# graphic_stereo_2.net
KiCad netlist of a schematic drawn in EAGLE
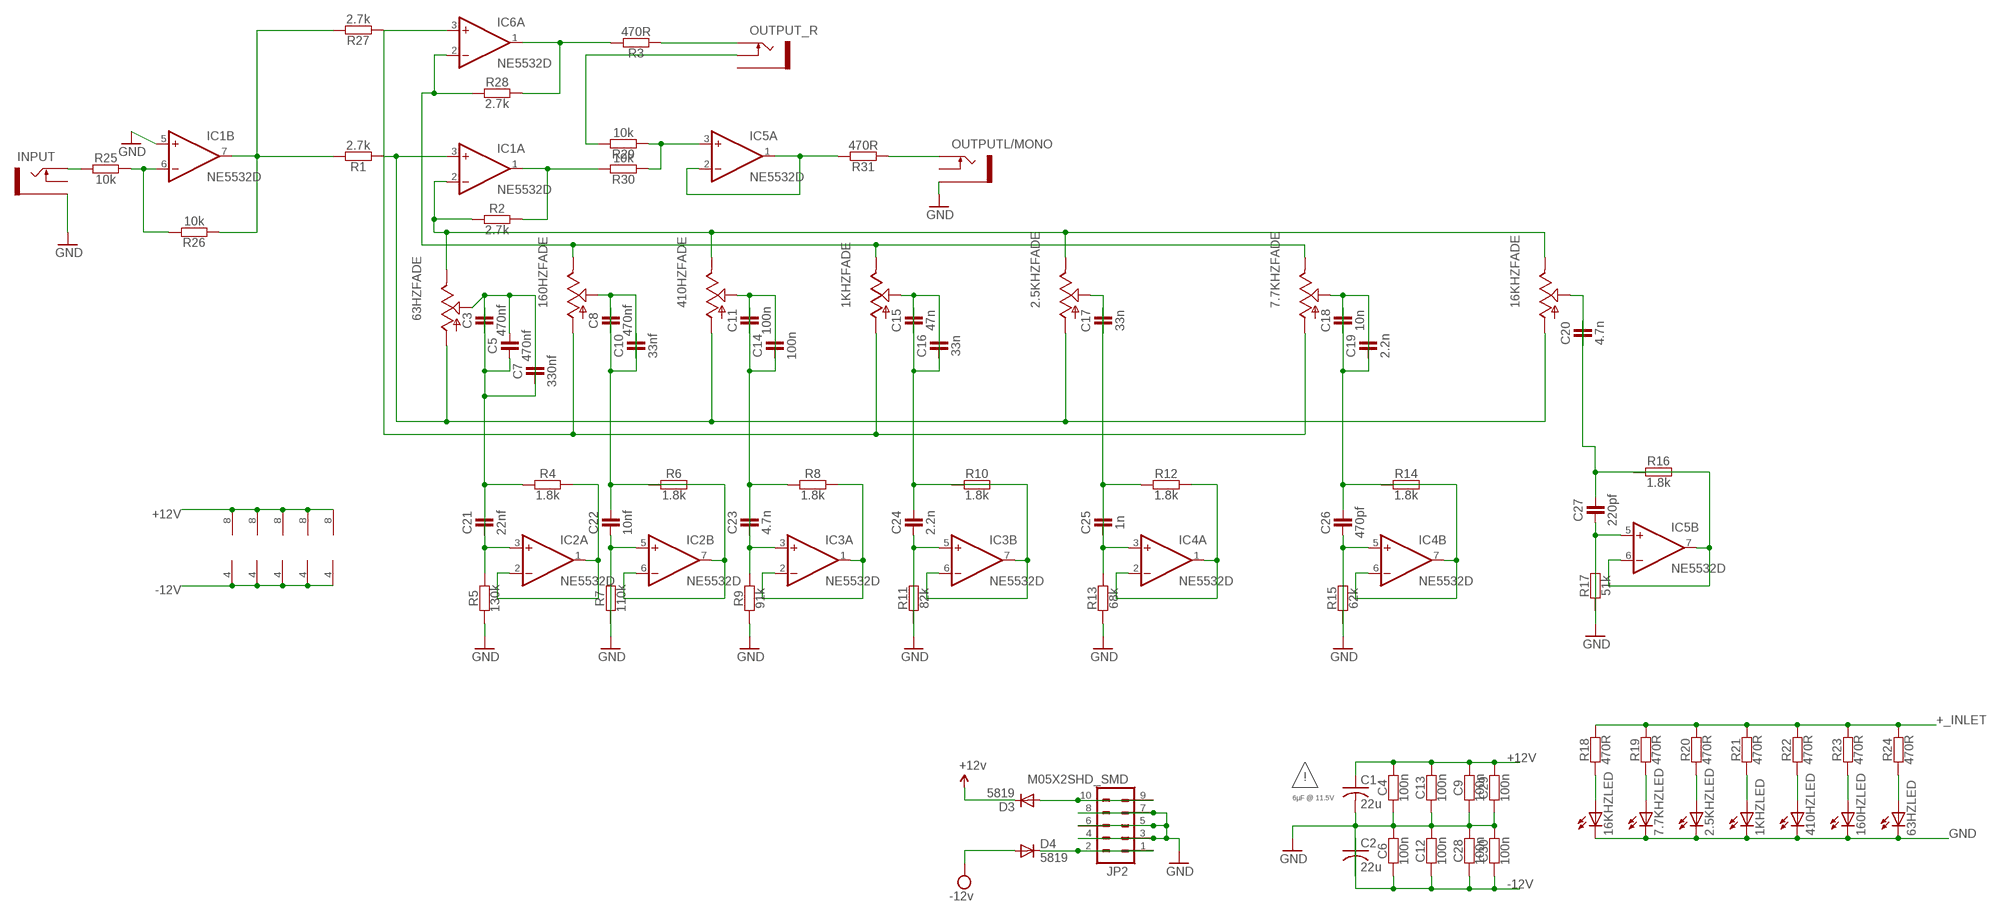
[diagram p0: schematic, sheet 1]

(export (version "E")
  (design (tool "Eeschema 10.0.6"))
  (components
    (comp (ref "1KHZ")
      (value "ALPHA_20MM_ILLUM_FADER")
      (footprint "eagle-import:ALPHA_ILL_FADER_20MM")
      (libsource (lib "eagle-import") (part "ALPHA_20MM_ILLUM_FADER"))
    )
    (comp (ref "2.5KHZ")
      (value "ALPHA_20MM_ILLUM_FADER")
      (footprint "eagle-import:ALPHA_ILL_FADER_20MM")
      (libsource (lib "eagle-import") (part "ALPHA_20MM_ILLUM_FADER"))
    )
    (comp (ref "7.7KHZ")
      (value "ALPHA_20MM_ILLUM_FADER")
      (footprint "eagle-import:ALPHA_ILL_FADER_20MM")
      (libsource (lib "eagle-import") (part "ALPHA_20MM_ILLUM_FADER"))
    )
    (comp (ref "16KHZ")
      (value "ALPHA_20MM_ILLUM_FADER")
      (footprint "eagle-import:ALPHA_ILL_FADER_20MM")
      (libsource (lib "eagle-import") (part "ALPHA_20MM_ILLUM_FADER"))
    )
    (comp (ref "63HZ")
      (value "ALPHA_20MM_ILLUM_FADER")
      (footprint "eagle-import:ALPHA_ILL_FADER_20MM")
      (libsource (lib "eagle-import") (part "ALPHA_20MM_ILLUM_FADER"))
    )
    (comp (ref "160HZ")
      (value "ALPHA_20MM_ILLUM_FADER")
      (footprint "eagle-import:ALPHA_ILL_FADER_20MM")
      (libsource (lib "eagle-import") (part "ALPHA_20MM_ILLUM_FADER"))
    )
    (comp (ref "410HZ")
      (value "ALPHA_20MM_ILLUM_FADER")
      (footprint "eagle-import:ALPHA_ILL_FADER_20MM")
      (libsource (lib "eagle-import") (part "ALPHA_20MM_ILLUM_FADER"))
    )
    (comp (ref "C1")
      (value "22u")
      (footprint "eagle-import:C1206")
      (libsource (lib "eagle-import") (part "C-USC1206"))
    )
    (comp (ref "C2")
      (value "22u")
      (footprint "eagle-import:C1206")
      (libsource (lib "eagle-import") (part "C-USC1206"))
    )
    (comp (ref "C3")
      (value "470nf")
      (footprint "eagle-import:C0805")
      (libsource (lib "eagle-import") (part "CAPACITOR-0805"))
    )
    (comp (ref "C4")
      (value "100n")
      (footprint "eagle-import:C0805")
      (libsource (lib "eagle-import") (part "RESISTOR-0805"))
    )
    (comp (ref "C5")
      (value "470nf")
      (footprint "eagle-import:C0805")
      (libsource (lib "eagle-import") (part "CAPACITOR-0805"))
    )
    (comp (ref "C6")
      (value "100n")
      (footprint "eagle-import:C0805")
      (libsource (lib "eagle-import") (part "RESISTOR-0805"))
    )
    (comp (ref "C7")
      (value "330nf")
      (footprint "eagle-import:C0805")
      (libsource (lib "eagle-import") (part "CAPACITOR-0805"))
    )
    (comp (ref "C8")
      (value "470nf")
      (footprint "eagle-import:C0805")
      (libsource (lib "eagle-import") (part "CAPACITOR-0805"))
    )
    (comp (ref "C9")
      (value "100n")
      (footprint "eagle-import:C0805")
      (libsource (lib "eagle-import") (part "RESISTOR-0805"))
    )
    (comp (ref "C10")
      (value "33nf")
      (footprint "eagle-import:C0805")
      (libsource (lib "eagle-import") (part "CAPACITOR-0805"))
    )
    (comp (ref "C11")
      (value "100n")
      (footprint "eagle-import:C0805")
      (libsource (lib "eagle-import") (part "CAPACITOR-0805"))
    )
    (comp (ref "C12")
      (value "100n")
      (footprint "eagle-import:C0805")
      (libsource (lib "eagle-import") (part "RESISTOR-0805"))
    )
    (comp (ref "C13")
      (value "100n")
      (footprint "eagle-import:C0805")
      (libsource (lib "eagle-import") (part "RESISTOR-0805"))
    )
    (comp (ref "C14")
      (value "100n")
      (footprint "eagle-import:C0805")
      (libsource (lib "eagle-import") (part "CAPACITOR-0805"))
    )
    (comp (ref "C15")
      (value "47n")
      (footprint "eagle-import:C0805")
      (libsource (lib "eagle-import") (part "CAPACITOR-0805"))
    )
    (comp (ref "C16")
      (value "33n")
      (footprint "eagle-import:C0805")
      (libsource (lib "eagle-import") (part "CAPACITOR-0805"))
    )
    (comp (ref "C17")
      (value "33n")
      (footprint "eagle-import:C0805")
      (libsource (lib "eagle-import") (part "CAPACITOR-0805"))
    )
    (comp (ref "C18")
      (value "10n")
      (footprint "eagle-import:C0805")
      (libsource (lib "eagle-import") (part "CAPACITOR-0805"))
    )
    (comp (ref "C19")
      (value "2.2n")
      (footprint "eagle-import:C0805")
      (libsource (lib "eagle-import") (part "CAPACITOR-0805"))
    )
    (comp (ref "C20")
      (value "4.7n")
      (footprint "eagle-import:C0805")
      (libsource (lib "eagle-import") (part "CAPACITOR-0805"))
    )
    (comp (ref "C21")
      (value "22nf")
      (footprint "eagle-import:C0805")
      (libsource (lib "eagle-import") (part "CAPACITOR-0805"))
    )
    (comp (ref "C22")
      (value "10nf")
      (footprint "eagle-import:C0805")
      (libsource (lib "eagle-import") (part "CAPACITOR-0805"))
    )
    (comp (ref "C23")
      (value "4.7n")
      (footprint "eagle-import:C0805")
      (libsource (lib "eagle-import") (part "CAPACITOR-0805"))
    )
    (comp (ref "C24")
      (value "2.2n")
      (footprint "eagle-import:C0805")
      (libsource (lib "eagle-import") (part "CAPACITOR-0805"))
    )
    (comp (ref "C25")
      (value "1n")
      (footprint "eagle-import:C0805")
      (libsource (lib "eagle-import") (part "CAPACITOR-0805"))
    )
    (comp (ref "C26")
      (value "470pf")
      (footprint "eagle-import:C0805")
      (libsource (lib "eagle-import") (part "CAPACITOR-0805"))
    )
    (comp (ref "C27")
      (value "220pf")
      (footprint "eagle-import:C0805")
      (libsource (lib "eagle-import") (part "CAPACITOR-0805"))
    )
    (comp (ref "C28")
      (value "100n")
      (footprint "eagle-import:C0805")
      (libsource (lib "eagle-import") (part "RESISTOR-0805"))
    )
    (comp (ref "C29")
      (value "100n")
      (footprint "eagle-import:C0805")
      (libsource (lib "eagle-import") (part "RESISTOR-0805"))
    )
    (comp (ref "C30")
      (value "100n")
      (footprint "eagle-import:C0805")
      (libsource (lib "eagle-import") (part "RESISTOR-0805"))
    )
    (comp (ref "D3")
      (value "5819")
      (footprint "eagle-import:SOD123")
      (libsource (lib "eagle-import") (part "DIODE-SOD123"))
    )
    (comp (ref "D4")
      (value "5819")
      (footprint "eagle-import:SOD123")
      (libsource (lib "eagle-import") (part "DIODE-SOD123"))
    )
    (comp (ref "IC1")
      (value "NE5532D")
      (footprint "eagle-import:SO08")
      (libsource (lib "eagle-import") (part "NE5532D"))
    )
    (comp (ref "IC2")
      (value "NE5532D")
      (footprint "eagle-import:SO08")
      (libsource (lib "eagle-import") (part "NE5532D"))
    )
    (comp (ref "IC3")
      (value "NE5532D")
      (footprint "eagle-import:SO08")
      (libsource (lib "eagle-import") (part "NE5532D"))
    )
    (comp (ref "IC4")
      (value "NE5532D")
      (footprint "eagle-import:SO08")
      (libsource (lib "eagle-import") (part "NE5532D"))
    )
    (comp (ref "IC5")
      (value "NE5532D")
      (footprint "eagle-import:SO08")
      (libsource (lib "eagle-import") (part "NE5532D"))
    )
    (comp (ref "IC6")
      (value "NE5532D")
      (footprint "eagle-import:SO08")
      (libsource (lib "eagle-import") (part "NE5532D"))
    )
    (comp (ref "INPUT")
      (value "THONKICONNNEW")
      (footprint "eagle-import:WQP-PJ301M-12_JACK")
      (libsource (lib "eagle-import") (part "THONKICONNNEW"))
    )
    (comp (ref "JP2")
      (value "M05X2SHD_SMD")
      (footprint "eagle-import:2X5-SHROUDED_SMD")
      (libsource (lib "eagle-import") (part "M05X2SHD_SMD"))
    )
    (comp (ref "OUTPUTL/MONO")
      (value "THONKICONNNEW")
      (footprint "eagle-import:WQP-PJ301M-12_JACK")
      (libsource (lib "eagle-import") (part "THONKICONNNEW"))
    )
    (comp (ref "OUTPUT_R")
      (value "THONKICONNNEW")
      (footprint "eagle-import:WQP-PJ301M-12_JACK")
      (libsource (lib "eagle-import") (part "THONKICONNNEW"))
    )
    (comp (ref "R1")
      (value "2.7k")
      (footprint "eagle-import:C0805")
      (libsource (lib "eagle-import") (part "RESISTOR-0805"))
    )
    (comp (ref "R2")
      (value "2.7k")
      (footprint "eagle-import:C0805")
      (libsource (lib "eagle-import") (part "RESISTOR-0805"))
    )
    (comp (ref "R3")
      (value "470R")
      (footprint "eagle-import:C0805")
      (libsource (lib "eagle-import") (part "RESISTOR-0805"))
    )
    (comp (ref "R4")
      (value "1.8k")
      (footprint "eagle-import:C0805")
      (libsource (lib "eagle-import") (part "RESISTOR-0805"))
    )
    (comp (ref "R5")
      (value "130k")
      (footprint "eagle-import:C0805")
      (libsource (lib "eagle-import") (part "RESISTOR-0805"))
    )
    (comp (ref "R6")
      (value "1.8k")
      (footprint "eagle-import:C0805")
      (libsource (lib "eagle-import") (part "RESISTOR-0805"))
    )
    (comp (ref "R7")
      (value "110k")
      (footprint "eagle-import:C0805")
      (libsource (lib "eagle-import") (part "RESISTOR-0805"))
    )
    (comp (ref "R8")
      (value "1.8k")
      (footprint "eagle-import:C0805")
      (libsource (lib "eagle-import") (part "RESISTOR-0805"))
    )
    (comp (ref "R9")
      (value "91k")
      (footprint "eagle-import:C0805")
      (libsource (lib "eagle-import") (part "RESISTOR-0805"))
    )
    (comp (ref "R10")
      (value "1.8k")
      (footprint "eagle-import:C0805")
      (libsource (lib "eagle-import") (part "RESISTOR-0805"))
    )
    (comp (ref "R11")
      (value "82k")
      (footprint "eagle-import:C0805")
      (libsource (lib "eagle-import") (part "RESISTOR-0805"))
    )
    (comp (ref "R12")
      (value "1.8k")
      (footprint "eagle-import:C0805")
      (libsource (lib "eagle-import") (part "RESISTOR-0805"))
    )
    (comp (ref "R13")
      (value "68k")
      (footprint "eagle-import:C0805")
      (libsource (lib "eagle-import") (part "RESISTOR-0805"))
    )
    (comp (ref "R14")
      (value "1.8k")
      (footprint "eagle-import:C0805")
      (libsource (lib "eagle-import") (part "RESISTOR-0805"))
    )
    (comp (ref "R15")
      (value "62k")
      (footprint "eagle-import:C0805")
      (libsource (lib "eagle-import") (part "RESISTOR-0805"))
    )
    (comp (ref "R16")
      (value "1.8k")
      (footprint "eagle-import:C0805")
      (libsource (lib "eagle-import") (part "RESISTOR-0805"))
    )
    (comp (ref "R17")
      (value "51k")
      (footprint "eagle-import:C0805")
      (libsource (lib "eagle-import") (part "RESISTOR-0805"))
    )
    (comp (ref "R18")
      (value "470R")
      (footprint "eagle-import:C0805")
      (libsource (lib "eagle-import") (part "RESISTOR-0805"))
    )
    (comp (ref "R19")
      (value "470R")
      (footprint "eagle-import:C0805")
      (libsource (lib "eagle-import") (part "RESISTOR-0805"))
    )
    (comp (ref "R20")
      (value "470R")
      (footprint "eagle-import:C0805")
      (libsource (lib "eagle-import") (part "RESISTOR-0805"))
    )
    (comp (ref "R21")
      (value "470R")
      (footprint "eagle-import:C0805")
      (libsource (lib "eagle-import") (part "RESISTOR-0805"))
    )
    (comp (ref "R22")
      (value "470R")
      (footprint "eagle-import:C0805")
      (libsource (lib "eagle-import") (part "RESISTOR-0805"))
    )
    (comp (ref "R23")
      (value "470R")
      (footprint "eagle-import:C0805")
      (libsource (lib "eagle-import") (part "RESISTOR-0805"))
    )
    (comp (ref "R24")
      (value "470R")
      (footprint "eagle-import:C0805")
      (libsource (lib "eagle-import") (part "RESISTOR-0805"))
    )
    (comp (ref "R25")
      (value "10k")
      (footprint "eagle-import:C0805")
      (libsource (lib "eagle-import") (part "RESISTOR-0805"))
    )
    (comp (ref "R26")
      (value "10k")
      (footprint "eagle-import:C0805")
      (libsource (lib "eagle-import") (part "RESISTOR-0805"))
    )
    (comp (ref "R27")
      (value "2.7k")
      (footprint "eagle-import:C0805")
      (libsource (lib "eagle-import") (part "RESISTOR-0805"))
    )
    (comp (ref "R28")
      (value "2.7k")
      (footprint "eagle-import:C0805")
      (libsource (lib "eagle-import") (part "RESISTOR-0805"))
    )
    (comp (ref "R29")
      (value "10k")
      (footprint "eagle-import:C0805")
      (libsource (lib "eagle-import") (part "RESISTOR-0805"))
    )
    (comp (ref "R30")
      (value "10k")
      (footprint "eagle-import:C0805")
      (libsource (lib "eagle-import") (part "RESISTOR-0805"))
    )
    (comp (ref "R31")
      (value "470R")
      (footprint "eagle-import:C0805")
      (libsource (lib "eagle-import") (part "RESISTOR-0805"))
    )
  )
  (nets
    (net (code "1") (name "+12v") (class "Default")
      (node (ref "C1") (pin "1") (pinfunction "1_1") (pintype "passive"))
      (node (ref "C13") (pin "2") (pinfunction "2_2") (pintype "passive"))
      (node (ref "C29") (pin "2") (pinfunction "2_2") (pintype "passive"))
      (node (ref "C4") (pin "2") (pinfunction "2_2") (pintype "passive"))
      (node (ref "C9") (pin "2") (pinfunction "2_2") (pintype "passive"))
      (node (ref "D3") (pin "C") (pinfunction "C_C") (pintype "passive"))
      (node (ref "IC1") (pin "8") (pinfunction "V+_8") (pintype "power_in"))
      (node (ref "IC2") (pin "8") (pinfunction "V+_8") (pintype "power_in"))
      (node (ref "IC3") (pin "8") (pinfunction "V+_8") (pintype "power_in"))
      (node (ref "IC4") (pin "8") (pinfunction "V+_8") (pintype "power_in"))
      (node (ref "IC5") (pin "8") (pinfunction "V+_8") (pintype "power_in"))
    )
    (net (code "2") (name "-12v") (class "Default")
      (node (ref "C12") (pin "1") (pinfunction "1_1") (pintype "passive"))
      (node (ref "C2") (pin "1") (pinfunction "1_1") (pintype "passive"))
      (node (ref "C28") (pin "1") (pinfunction "1_1") (pintype "passive"))
      (node (ref "C30") (pin "1") (pinfunction "1_1") (pintype "passive"))
      (node (ref "C6") (pin "1") (pinfunction "1_1") (pintype "passive"))
      (node (ref "D4") (pin "A") (pinfunction "A_A") (pintype "passive"))
      (node (ref "IC1") (pin "4") (pinfunction "V-_4") (pintype "power_in"))
      (node (ref "IC2") (pin "4") (pinfunction "V-_4") (pintype "power_in"))
      (node (ref "IC3") (pin "4") (pinfunction "V-_4") (pintype "power_in"))
      (node (ref "IC4") (pin "4") (pinfunction "V-_4") (pintype "power_in"))
      (node (ref "IC5") (pin "4") (pinfunction "V-_4") (pintype "power_in"))
    )
    (net (code "3") (name "/+_INLET") (class "Default")
      (node (ref "D3") (pin "A") (pinfunction "A_A") (pintype "passive"))
      (node (ref "JP2") (pin "10") (pinfunction "10_10") (pintype "passive"))
      (node (ref "JP2") (pin "9") (pinfunction "9_9") (pintype "passive"))
      (node (ref "R18") (pin "2") (pinfunction "2_2") (pintype "passive"))
      (node (ref "R19") (pin "2") (pinfunction "2_2") (pintype "passive"))
      (node (ref "R20") (pin "2") (pinfunction "2_2") (pintype "passive"))
      (node (ref "R21") (pin "2") (pinfunction "2_2") (pintype "passive"))
      (node (ref "R22") (pin "2") (pinfunction "2_2") (pintype "passive"))
      (node (ref "R23") (pin "2") (pinfunction "2_2") (pintype "passive"))
      (node (ref "R24") (pin "2") (pinfunction "2_2") (pintype "passive"))
    )
    (net (code "4") (name "GND") (class "Default")
      (node (ref "160HZ") (pin "E") (pinfunction "C_E") (pintype "passive"))
      (node (ref "16KHZ") (pin "E") (pinfunction "C_E") (pintype "passive"))
      (node (ref "1KHZ") (pin "E") (pinfunction "C_E") (pintype "passive"))
      (node (ref "2.5KHZ") (pin "E") (pinfunction "C_E") (pintype "passive"))
      (node (ref "410HZ") (pin "E") (pinfunction "C_E") (pintype "passive"))
      (node (ref "63HZ") (pin "E") (pinfunction "C_E") (pintype "passive"))
      (node (ref "7.7KHZ") (pin "E") (pinfunction "C_E") (pintype "passive"))
      (node (ref "C1") (pin "2") (pinfunction "2_2") (pintype "passive"))
      (node (ref "C12") (pin "2") (pinfunction "2_2") (pintype "passive"))
      (node (ref "C13") (pin "1") (pinfunction "1_1") (pintype "passive"))
      (node (ref "C2") (pin "2") (pinfunction "2_2") (pintype "passive"))
      (node (ref "C28") (pin "2") (pinfunction "2_2") (pintype "passive"))
      (node (ref "C29") (pin "1") (pinfunction "1_1") (pintype "passive"))
      (node (ref "C30") (pin "2") (pinfunction "2_2") (pintype "passive"))
      (node (ref "C4") (pin "1") (pinfunction "1_1") (pintype "passive"))
      (node (ref "C6") (pin "2") (pinfunction "2_2") (pintype "passive"))
      (node (ref "C9") (pin "1") (pinfunction "1_1") (pintype "passive"))
      (node (ref "IC1") (pin "5") (pinfunction "+IN_5") (pintype "input"))
      (node (ref "INPUT") (pin "P$3_SLEEVE") (pinfunction "SLEEVE_P$3_SLEEVE") (pintype "passive"))
      (node (ref "JP2") (pin "3") (pinfunction "3_3") (pintype "passive"))
      (node (ref "JP2") (pin "4") (pinfunction "4_4") (pintype "passive"))
      (node (ref "JP2") (pin "5") (pinfunction "5_5") (pintype "passive"))
      (node (ref "JP2") (pin "6") (pinfunction "6_6") (pintype "passive"))
      (node (ref "JP2") (pin "7") (pinfunction "7_7") (pintype "passive"))
      (node (ref "JP2") (pin "8") (pinfunction "8_8") (pintype "passive"))
      (node (ref "OUTPUTL/MONO") (pin "P$3_SLEEVE") (pinfunction "SLEEVE_P$3_SLEEVE") (pintype "passive"))
      (node (ref "R11") (pin "2") (pinfunction "2_2") (pintype "passive"))
      (node (ref "R13") (pin "1") (pinfunction "1_1") (pintype "passive"))
      (node (ref "R15") (pin "2") (pinfunction "2_2") (pintype "passive"))
      (node (ref "R17") (pin "2") (pinfunction "2_2") (pintype "passive"))
      (node (ref "R5") (pin "1") (pinfunction "1_1") (pintype "passive"))
      (node (ref "R7") (pin "2") (pinfunction "2_2") (pintype "passive"))
      (node (ref "R9") (pin "1") (pinfunction "1_1") (pintype "passive"))
    )
    (net (code "5") (name "Net-(1KHZA-S)") (class "Default")
      (node (ref "1KHZ") (pin "2") (pinfunction "S_2") (pintype "passive"))
      (node (ref "C15") (pin "1") (pinfunction "1_1") (pintype "passive"))
      (node (ref "C16") (pin "1") (pinfunction "1_1") (pintype "passive"))
    )
    (net (code "6") (name "Net-(1KHZB-A)") (class "Default")
      (node (ref "1KHZ") (pin "B") (pinfunction "A_B") (pintype "passive"))
      (node (ref "R21") (pin "1") (pinfunction "1_1") (pintype "passive"))
    )
    (net (code "7") (name "Net-(2.5KHZA-S)") (class "Default")
      (node (ref "2.5KHZ") (pin "2") (pinfunction "S_2") (pintype "passive"))
      (node (ref "C17") (pin "1") (pinfunction "1_1") (pintype "passive"))
    )
    (net (code "8") (name "Net-(2.5KHZB-A)") (class "Default")
      (node (ref "2.5KHZ") (pin "B") (pinfunction "A_B") (pintype "passive"))
      (node (ref "R20") (pin "1") (pinfunction "1_1") (pintype "passive"))
    )
    (net (code "9") (name "Net-(7.7KHZA-S)") (class "Default")
      (node (ref "7.7KHZ") (pin "2") (pinfunction "S_2") (pintype "passive"))
      (node (ref "C18") (pin "1") (pinfunction "1_1") (pintype "passive"))
      (node (ref "C19") (pin "1") (pinfunction "1_1") (pintype "passive"))
    )
    (net (code "10") (name "Net-(7.7KHZB-A)") (class "Default")
      (node (ref "7.7KHZ") (pin "B") (pinfunction "A_B") (pintype "passive"))
      (node (ref "R19") (pin "1") (pinfunction "1_1") (pintype "passive"))
    )
    (net (code "11") (name "Net-(16KHZA-A)") (class "Default")
      (node (ref "16KHZ") (pin "3") (pinfunction "A_3") (pintype "passive"))
      (node (ref "2.5KHZ") (pin "3") (pinfunction "A_3") (pintype "passive"))
      (node (ref "410HZ") (pin "3") (pinfunction "A_3") (pintype "passive"))
      (node (ref "63HZ") (pin "3") (pinfunction "A_3") (pintype "passive"))
      (node (ref "IC1") (pin "3") (pinfunction "+IN_3") (pintype "input"))
      (node (ref "R1") (pin "1") (pinfunction "1_1") (pintype "passive"))
    )
    (net (code "12") (name "Net-(16KHZA-E)") (class "Default")
      (node (ref "16KHZ") (pin "1") (pinfunction "E_1") (pintype "passive"))
      (node (ref "2.5KHZ") (pin "1") (pinfunction "E_1") (pintype "passive"))
      (node (ref "410HZ") (pin "1") (pinfunction "E_1") (pintype "passive"))
      (node (ref "63HZ") (pin "1") (pinfunction "E_1") (pintype "passive"))
      (node (ref "IC1") (pin "2") (pinfunction "-IN_2") (pintype "input"))
      (node (ref "R2") (pin "1") (pinfunction "1_1") (pintype "passive"))
    )
    (net (code "13") (name "Net-(16KHZA-S)") (class "Default")
      (node (ref "16KHZ") (pin "2") (pinfunction "S_2") (pintype "passive"))
      (node (ref "C20") (pin "1") (pinfunction "1_1") (pintype "passive"))
    )
    (net (code "14") (name "Net-(16KHZB-A)") (class "Default")
      (node (ref "16KHZ") (pin "B") (pinfunction "A_B") (pintype "passive"))
      (node (ref "R18") (pin "1") (pinfunction "1_1") (pintype "passive"))
    )
    (net (code "15") (name "Net-(63HZA-S)") (class "Default")
      (node (ref "63HZ") (pin "2") (pinfunction "S_2") (pintype "passive"))
      (node (ref "C3") (pin "1") (pinfunction "1_1") (pintype "passive"))
      (node (ref "C5") (pin "2") (pinfunction "2_2") (pintype "passive"))
      (node (ref "C7") (pin "1") (pinfunction "1_1") (pintype "passive"))
    )
    (net (code "16") (name "Net-(63HZB-A)") (class "Default")
      (node (ref "63HZ") (pin "B") (pinfunction "A_B") (pintype "passive"))
      (node (ref "R24") (pin "1") (pinfunction "1_1") (pintype "passive"))
    )
    (net (code "17") (name "Net-(160HZA-A)") (class "Default")
      (node (ref "160HZ") (pin "3") (pinfunction "A_3") (pintype "passive"))
      (node (ref "1KHZ") (pin "3") (pinfunction "A_3") (pintype "passive"))
      (node (ref "7.7KHZ") (pin "3") (pinfunction "A_3") (pintype "passive"))
      (node (ref "IC6") (pin "3") (pinfunction "+IN_3") (pintype "input"))
      (node (ref "R27") (pin "1") (pinfunction "1_1") (pintype "passive"))
    )
    (net (code "18") (name "Net-(160HZA-E)") (class "Default")
      (node (ref "160HZ") (pin "1") (pinfunction "E_1") (pintype "passive"))
      (node (ref "1KHZ") (pin "1") (pinfunction "E_1") (pintype "passive"))
      (node (ref "7.7KHZ") (pin "1") (pinfunction "E_1") (pintype "passive"))
      (node (ref "IC6") (pin "2") (pinfunction "-IN_2") (pintype "input"))
      (node (ref "R28") (pin "1") (pinfunction "1_1") (pintype "passive"))
    )
    (net (code "19") (name "Net-(160HZA-S)") (class "Default")
      (node (ref "160HZ") (pin "2") (pinfunction "S_2") (pintype "passive"))
      (node (ref "C10") (pin "1") (pinfunction "1_1") (pintype "passive"))
      (node (ref "C8") (pin "1") (pinfunction "1_1") (pintype "passive"))
    )
    (net (code "20") (name "Net-(160HZB-A)") (class "Default")
      (node (ref "160HZ") (pin "B") (pinfunction "A_B") (pintype "passive"))
      (node (ref "R23") (pin "1") (pinfunction "1_1") (pintype "passive"))
    )
    (net (code "21") (name "Net-(410HZA-S)") (class "Default")
      (node (ref "410HZ") (pin "2") (pinfunction "S_2") (pintype "passive"))
      (node (ref "C11") (pin "1") (pinfunction "1_1") (pintype "passive"))
      (node (ref "C14") (pin "1") (pinfunction "1_1") (pintype "passive"))
    )
    (net (code "22") (name "Net-(410HZB-A)") (class "Default")
      (node (ref "410HZ") (pin "B") (pinfunction "A_B") (pintype "passive"))
      (node (ref "R22") (pin "1") (pinfunction "1_1") (pintype "passive"))
    )
    (net (code "23") (name "Net-(C10-Pad2)") (class "Default")
      (node (ref "C10") (pin "2") (pinfunction "2_2") (pintype "passive"))
      (node (ref "C22") (pin "2") (pinfunction "2_2") (pintype "passive"))
      (node (ref "C8") (pin "2") (pinfunction "2_2") (pintype "passive"))
      (node (ref "R6") (pin "2") (pinfunction "2_2") (pintype "passive"))
    )
    (net (code "24") (name "Net-(C11-Pad2)") (class "Default")
      (node (ref "C11") (pin "2") (pinfunction "2_2") (pintype "passive"))
      (node (ref "C14") (pin "2") (pinfunction "2_2") (pintype "passive"))
      (node (ref "C23") (pin "1") (pinfunction "1_1") (pintype "passive"))
      (node (ref "R8") (pin "1") (pinfunction "1_1") (pintype "passive"))
    )
    (net (code "25") (name "Net-(C15-Pad2)") (class "Default")
      (node (ref "C15") (pin "2") (pinfunction "2_2") (pintype "passive"))
      (node (ref "C16") (pin "2") (pinfunction "2_2") (pintype "passive"))
      (node (ref "C24") (pin "2") (pinfunction "2_2") (pintype "passive"))
      (node (ref "R10") (pin "2") (pinfunction "2_2") (pintype "passive"))
    )
    (net (code "26") (name "Net-(C17-Pad2)") (class "Default")
      (node (ref "C17") (pin "2") (pinfunction "2_2") (pintype "passive"))
      (node (ref "C25") (pin "1") (pinfunction "1_1") (pintype "passive"))
      (node (ref "R12") (pin "1") (pinfunction "1_1") (pintype "passive"))
    )
    (net (code "27") (name "Net-(C18-Pad2)") (class "Default")
      (node (ref "C18") (pin "2") (pinfunction "2_2") (pintype "passive"))
      (node (ref "C19") (pin "2") (pinfunction "2_2") (pintype "passive"))
      (node (ref "C26") (pin "2") (pinfunction "2_2") (pintype "passive"))
      (node (ref "R14") (pin "2") (pinfunction "2_2") (pintype "passive"))
    )
    (net (code "28") (name "Net-(C20-Pad2)") (class "Default")
      (node (ref "C20") (pin "2") (pinfunction "2_2") (pintype "passive"))
      (node (ref "C27") (pin "2") (pinfunction "2_2") (pintype "passive"))
      (node (ref "R16") (pin "2") (pinfunction "2_2") (pintype "passive"))
    )
    (net (code "29") (name "Net-(C21-Pad1)") (class "Default")
      (node (ref "C21") (pin "1") (pinfunction "1_1") (pintype "passive"))
      (node (ref "C3") (pin "2") (pinfunction "2_2") (pintype "passive"))
      (node (ref "C5") (pin "1") (pinfunction "1_1") (pintype "passive"))
      (node (ref "C7") (pin "2") (pinfunction "2_2") (pintype "passive"))
      (node (ref "R4") (pin "1") (pinfunction "1_1") (pintype "passive"))
    )
    (net (code "30") (name "Net-(D4-PadC)") (class "Default")
      (node (ref "D4") (pin "C") (pinfunction "C_C") (pintype "passive"))
      (node (ref "JP2") (pin "1") (pinfunction "1_1") (pintype "passive"))
      (node (ref "JP2") (pin "2") (pinfunction "2_2") (pintype "passive"))
    )
    (net (code "31") (name "Net-(IC1A-OUT)") (class "Default")
      (node (ref "IC1") (pin "1") (pinfunction "OUT_1") (pintype "output"))
      (node (ref "R2") (pin "2") (pinfunction "2_2") (pintype "passive"))
      (node (ref "R30") (pin "2") (pinfunction "2_2") (pintype "passive"))
    )
    (net (code "32") (name "Net-(IC1B--IN)") (class "Default")
      (node (ref "IC1") (pin "6") (pinfunction "-IN_6") (pintype "input"))
      (node (ref "R25") (pin "2") (pinfunction "2_2") (pintype "passive"))
      (node (ref "R26") (pin "2") (pinfunction "2_2") (pintype "passive"))
    )
    (net (code "33") (name "Net-(IC1B-OUT)") (class "Default")
      (node (ref "IC1") (pin "7") (pinfunction "OUT_7") (pintype "output"))
      (node (ref "R1") (pin "2") (pinfunction "2_2") (pintype "passive"))
      (node (ref "R26") (pin "1") (pinfunction "1_1") (pintype "passive"))
      (node (ref "R27") (pin "2") (pinfunction "2_2") (pintype "passive"))
    )
    (net (code "34") (name "Net-(IC2A-+IN)") (class "Default")
      (node (ref "C21") (pin "2") (pinfunction "2_2") (pintype "passive"))
      (node (ref "IC2") (pin "3") (pinfunction "+IN_3") (pintype "input"))
      (node (ref "R5") (pin "2") (pinfunction "2_2") (pintype "passive"))
    )
    (net (code "35") (name "Net-(IC2A--IN)") (class "Default")
      (node (ref "IC2") (pin "1") (pinfunction "OUT_1") (pintype "output"))
      (node (ref "IC2") (pin "2") (pinfunction "-IN_2") (pintype "input"))
      (node (ref "R4") (pin "2") (pinfunction "2_2") (pintype "passive"))
    )
    (net (code "36") (name "Net-(IC2B-+IN)") (class "Default")
      (node (ref "C22") (pin "1") (pinfunction "1_1") (pintype "passive"))
      (node (ref "IC2") (pin "5") (pinfunction "+IN_5") (pintype "input"))
      (node (ref "R7") (pin "1") (pinfunction "1_1") (pintype "passive"))
    )
    (net (code "37") (name "Net-(IC2B--IN)") (class "Default")
      (node (ref "IC2") (pin "6") (pinfunction "-IN_6") (pintype "input"))
      (node (ref "IC2") (pin "7") (pinfunction "OUT_7") (pintype "output"))
      (node (ref "R6") (pin "1") (pinfunction "1_1") (pintype "passive"))
    )
    (net (code "38") (name "Net-(IC3A-+IN)") (class "Default")
      (node (ref "C23") (pin "2") (pinfunction "2_2") (pintype "passive"))
      (node (ref "IC3") (pin "3") (pinfunction "+IN_3") (pintype "input"))
      (node (ref "R9") (pin "2") (pinfunction "2_2") (pintype "passive"))
    )
    (net (code "39") (name "Net-(IC3A--IN)") (class "Default")
      (node (ref "IC3") (pin "1") (pinfunction "OUT_1") (pintype "output"))
      (node (ref "IC3") (pin "2") (pinfunction "-IN_2") (pintype "input"))
      (node (ref "R8") (pin "2") (pinfunction "2_2") (pintype "passive"))
    )
    (net (code "40") (name "Net-(IC3B-+IN)") (class "Default")
      (node (ref "C24") (pin "1") (pinfunction "1_1") (pintype "passive"))
      (node (ref "IC3") (pin "5") (pinfunction "+IN_5") (pintype "input"))
      (node (ref "R11") (pin "1") (pinfunction "1_1") (pintype "passive"))
    )
    (net (code "41") (name "Net-(IC3B--IN)") (class "Default")
      (node (ref "IC3") (pin "6") (pinfunction "-IN_6") (pintype "input"))
      (node (ref "IC3") (pin "7") (pinfunction "OUT_7") (pintype "output"))
      (node (ref "R10") (pin "1") (pinfunction "1_1") (pintype "passive"))
    )
    (net (code "42") (name "Net-(IC4A-+IN)") (class "Default")
      (node (ref "C25") (pin "2") (pinfunction "2_2") (pintype "passive"))
      (node (ref "IC4") (pin "3") (pinfunction "+IN_3") (pintype "input"))
      (node (ref "R13") (pin "2") (pinfunction "2_2") (pintype "passive"))
    )
    (net (code "43") (name "Net-(IC4A--IN)") (class "Default")
      (node (ref "IC4") (pin "1") (pinfunction "OUT_1") (pintype "output"))
      (node (ref "IC4") (pin "2") (pinfunction "-IN_2") (pintype "input"))
      (node (ref "R12") (pin "2") (pinfunction "2_2") (pintype "passive"))
    )
    (net (code "44") (name "Net-(IC4B-+IN)") (class "Default")
      (node (ref "C26") (pin "1") (pinfunction "1_1") (pintype "passive"))
      (node (ref "IC4") (pin "5") (pinfunction "+IN_5") (pintype "input"))
      (node (ref "R15") (pin "1") (pinfunction "1_1") (pintype "passive"))
    )
    (net (code "45") (name "Net-(IC4B--IN)") (class "Default")
      (node (ref "IC4") (pin "6") (pinfunction "-IN_6") (pintype "input"))
      (node (ref "IC4") (pin "7") (pinfunction "OUT_7") (pintype "output"))
      (node (ref "R14") (pin "1") (pinfunction "1_1") (pintype "passive"))
    )
    (net (code "46") (name "Net-(IC5A-+IN)") (class "Default")
      (node (ref "IC5") (pin "3") (pinfunction "+IN_3") (pintype "input"))
      (node (ref "R29") (pin "1") (pinfunction "1_1") (pintype "passive"))
      (node (ref "R30") (pin "1") (pinfunction "1_1") (pintype "passive"))
    )
    (net (code "47") (name "Net-(IC5A--IN)") (class "Default")
      (node (ref "IC5") (pin "1") (pinfunction "OUT_1") (pintype "output"))
      (node (ref "IC5") (pin "2") (pinfunction "-IN_2") (pintype "input"))
      (node (ref "R31") (pin "2") (pinfunction "2_2") (pintype "passive"))
    )
    (net (code "48") (name "Net-(IC5B-+IN)") (class "Default")
      (node (ref "C27") (pin "1") (pinfunction "1_1") (pintype "passive"))
      (node (ref "IC5") (pin "5") (pinfunction "+IN_5") (pintype "input"))
      (node (ref "R17") (pin "1") (pinfunction "1_1") (pintype "passive"))
    )
    (net (code "49") (name "Net-(IC5B--IN)") (class "Default")
      (node (ref "IC5") (pin "6") (pinfunction "-IN_6") (pintype "input"))
      (node (ref "IC5") (pin "7") (pinfunction "OUT_7") (pintype "output"))
      (node (ref "R16") (pin "1") (pinfunction "1_1") (pintype "passive"))
    )
    (net (code "50") (name "Net-(IC6A-OUT)") (class "Default")
      (node (ref "IC6") (pin "1") (pinfunction "OUT_1") (pintype "output"))
      (node (ref "R28") (pin "2") (pinfunction "2_2") (pintype "passive"))
      (node (ref "R3") (pin "2") (pinfunction "2_2") (pintype "passive"))
    )
    (net (code "51") (name "Net-(INPUT-TIP)") (class "Default")
      (node (ref "INPUT") (pin "P$1_TIP") (pinfunction "TIP_P$1_TIP") (pintype "passive"))
      (node (ref "R25") (pin "1") (pinfunction "1_1") (pintype "passive"))
    )
    (net (code "52") (name "Net-(OUTPUTL/MONO-TIP)") (class "Default")
      (node (ref "OUTPUTL/MONO") (pin "P$1_TIP") (pinfunction "TIP_P$1_TIP") (pintype "passive"))
      (node (ref "R31") (pin "1") (pinfunction "1_1") (pintype "passive"))
    )
    (net (code "53") (name "Net-(OUTPUT_R-SWITCH)") (class "Default")
      (node (ref "OUTPUT_R") (pin "P$2_SWITCH") (pinfunction "SWITCH_P$2_SWITCH") (pintype "passive"))
      (node (ref "R29") (pin "2") (pinfunction "2_2") (pintype "passive"))
    )
    (net (code "54") (name "Net-(OUTPUT_R-TIP)") (class "Default")
      (node (ref "OUTPUT_R") (pin "P$1_TIP") (pinfunction "TIP_P$1_TIP") (pintype "passive"))
      (node (ref "R3") (pin "1") (pinfunction "1_1") (pintype "passive"))
    )
    (net (code "55") (name "unconnected-(INPUT-SWITCH-PadP$2_SWITCH)") (class "Default")
      (node (ref "INPUT") (pin "P$2_SWITCH") (pinfunction "SWITCH_P$2_SWITCH") (pintype "passive"))
    )
    (net (code "56") (name "unconnected-(OUTPUTL/MONO-SWITCH-PadP$2_SWITCH)") (class "Default")
      (node (ref "OUTPUTL/MONO") (pin "P$2_SWITCH") (pinfunction "SWITCH_P$2_SWITCH") (pintype "passive"))
    )
    (net (code "57") (name "unconnected-(OUTPUT_R-SLEEVE-PadP$3_SLEEVE)") (class "Default")
      (node (ref "OUTPUT_R") (pin "P$3_SLEEVE") (pinfunction "SLEEVE_P$3_SLEEVE") (pintype "passive"))
    )
  )
)
